# B7D_1_1.net
KiCad netlist of a schematic drawn in EAGLE
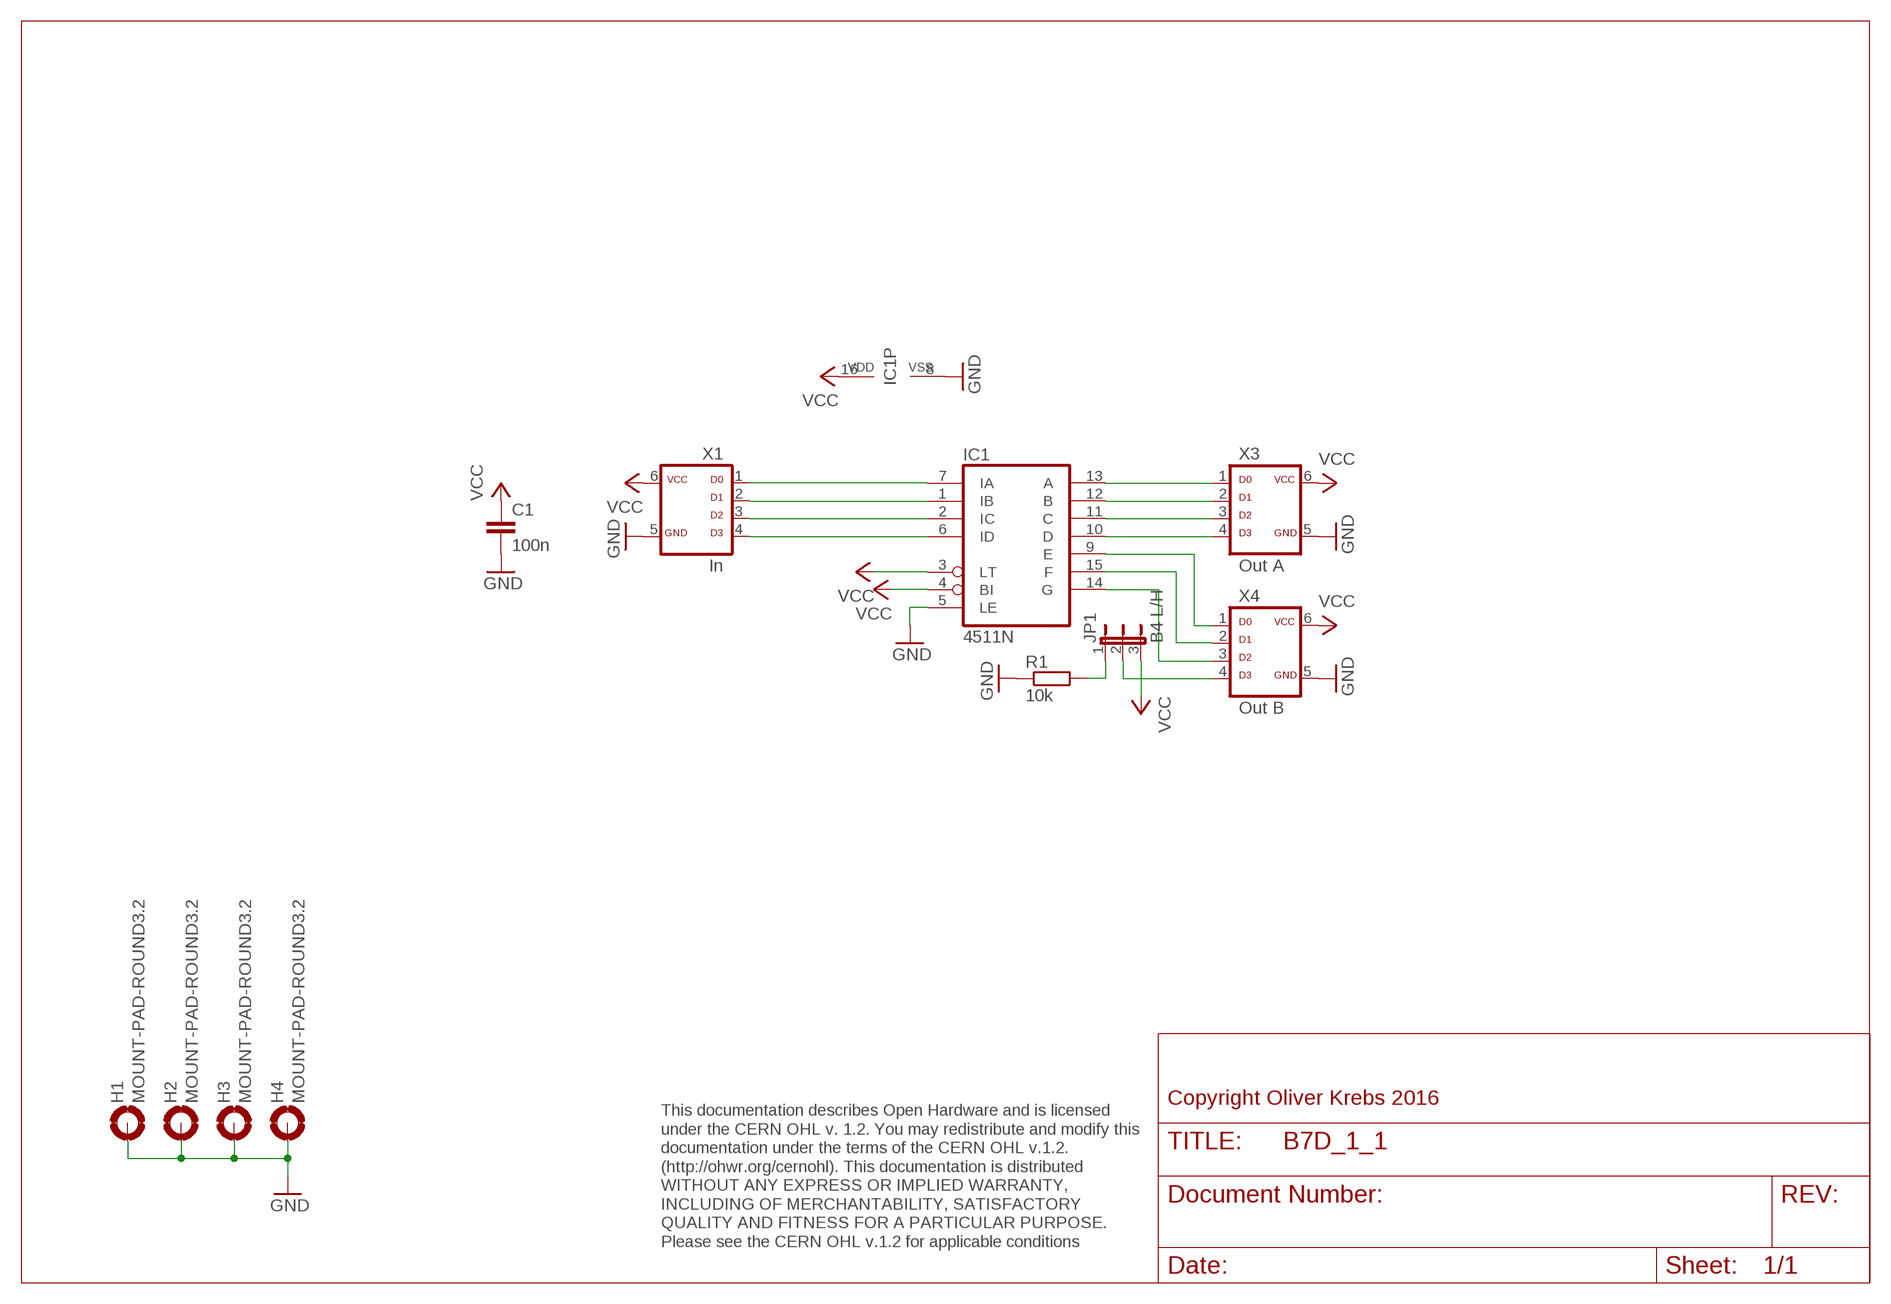
[diagram p0: schematic, sheet 1]

(export (version "E")
  (design (tool "Eeschema 10.0.6"))
  (components
    (comp (ref "C1")
      (value "100n")
      (footprint "eagle-import:C050-025X075")
      (libsource (lib "eagle-import") (part "C-EU050-025X075"))
    )
    (comp (ref "H1")
      (value "MOUNT-PAD-ROUND3.2")
      (footprint "eagle-import:3,2-PAD")
      (libsource (lib "eagle-import") (part "MOUNT-PAD-ROUND3.2"))
    )
    (comp (ref "H2")
      (value "MOUNT-PAD-ROUND3.2")
      (footprint "eagle-import:3,2-PAD")
      (libsource (lib "eagle-import") (part "MOUNT-PAD-ROUND3.2"))
    )
    (comp (ref "H3")
      (value "MOUNT-PAD-ROUND3.2")
      (footprint "eagle-import:3,2-PAD")
      (libsource (lib "eagle-import") (part "MOUNT-PAD-ROUND3.2"))
    )
    (comp (ref "H4")
      (value "MOUNT-PAD-ROUND3.2")
      (footprint "eagle-import:3,2-PAD")
      (libsource (lib "eagle-import") (part "MOUNT-PAD-ROUND3.2"))
    )
    (comp (ref "IC1")
      (value "4511N")
      (footprint "eagle-import:DIL16")
      (libsource (lib "eagle-import") (part "4511N"))
    )
    (comp (ref "JP1")
      (value "B4 L/H")
      (footprint "eagle-import:JP2")
      (libsource (lib "eagle-import") (part "JP2E"))
    )
    (comp (ref "R1")
      (value "10k")
      (footprint "eagle-import:0207_10")
      (libsource (lib "eagle-import") (part "R-EU_0207/10"))
    )
    (comp (ref "X1")
      (value "In")
      (footprint "eagle-import:ML-6")
      (libsource (lib "eagle-import") (part "ML6D"))
    )
    (comp (ref "X3")
      (value "Out A")
      (footprint "eagle-import:ML-6")
      (libsource (lib "eagle-import") (part "ML6D"))
    )
    (comp (ref "X4")
      (value "Out B")
      (footprint "eagle-import:ML-6")
      (libsource (lib "eagle-import") (part "ML6D"))
    )
  )
  (nets
    (net (code "1") (name "GND") (class "Default")
      (node (ref "C1") (pin "2") (pinfunction "2_2") (pintype "passive"))
      (node (ref "H1") (pin "B3,2") (pinfunction "MOUNT_B3,2") (pintype "passive"))
      (node (ref "H2") (pin "B3,2") (pinfunction "MOUNT_B3,2") (pintype "passive"))
      (node (ref "H3") (pin "B3,2") (pinfunction "MOUNT_B3,2") (pintype "passive"))
      (node (ref "H4") (pin "B3,2") (pinfunction "MOUNT_B3,2") (pintype "passive"))
      (node (ref "IC1") (pin "5") (pinfunction "LE_5") (pintype "input"))
      (node (ref "IC1") (pin "8") (pinfunction "VSS_8") (pintype "power_in"))
      (node (ref "R1") (pin "1") (pinfunction "1_1") (pintype "passive"))
      (node (ref "X1") (pin "5") (pinfunction "5_5") (pintype "passive"))
      (node (ref "X3") (pin "5") (pinfunction "5_5") (pintype "passive"))
      (node (ref "X4") (pin "5") (pinfunction "5_5") (pintype "passive"))
    )
    (net (code "2") (name "Net-(IC1A-A)") (class "Default")
      (node (ref "IC1") (pin "13") (pinfunction "A_13") (pintype "output"))
      (node (ref "X3") (pin "1") (pinfunction "1_1") (pintype "passive"))
    )
    (net (code "3") (name "Net-(IC1A-B)") (class "Default")
      (node (ref "IC1") (pin "12") (pinfunction "B_12") (pintype "output"))
      (node (ref "X3") (pin "2") (pinfunction "2_2") (pintype "passive"))
    )
    (net (code "4") (name "Net-(IC1A-C)") (class "Default")
      (node (ref "IC1") (pin "11") (pinfunction "C_11") (pintype "output"))
      (node (ref "X3") (pin "3") (pinfunction "3_3") (pintype "passive"))
    )
    (net (code "5") (name "Net-(IC1A-D)") (class "Default")
      (node (ref "IC1") (pin "10") (pinfunction "D_10") (pintype "output"))
      (node (ref "X3") (pin "4") (pinfunction "4_4") (pintype "passive"))
    )
    (net (code "6") (name "Net-(IC1A-E)") (class "Default")
      (node (ref "IC1") (pin "9") (pinfunction "E_9") (pintype "output"))
      (node (ref "X4") (pin "1") (pinfunction "1_1") (pintype "passive"))
    )
    (net (code "7") (name "Net-(IC1A-F)") (class "Default")
      (node (ref "IC1") (pin "15") (pinfunction "F_15") (pintype "output"))
      (node (ref "X4") (pin "2") (pinfunction "2_2") (pintype "passive"))
    )
    (net (code "8") (name "Net-(IC1A-G)") (class "Default")
      (node (ref "IC1") (pin "14") (pinfunction "G_14") (pintype "output"))
      (node (ref "X4") (pin "3") (pinfunction "3_3") (pintype "passive"))
    )
    (net (code "9") (name "Net-(IC1A-IA)") (class "Default")
      (node (ref "IC1") (pin "7") (pinfunction "IA_7") (pintype "input"))
      (node (ref "X1") (pin "1") (pinfunction "1_1") (pintype "passive"))
    )
    (net (code "10") (name "Net-(IC1A-IB)") (class "Default")
      (node (ref "IC1") (pin "1") (pinfunction "IB_1") (pintype "input"))
      (node (ref "X1") (pin "2") (pinfunction "2_2") (pintype "passive"))
    )
    (net (code "11") (name "Net-(IC1A-IC)") (class "Default")
      (node (ref "IC1") (pin "2") (pinfunction "IC_2") (pintype "input"))
      (node (ref "X1") (pin "3") (pinfunction "3_3") (pintype "passive"))
    )
    (net (code "12") (name "Net-(IC1A-ID)") (class "Default")
      (node (ref "IC1") (pin "6") (pinfunction "ID_6") (pintype "input"))
      (node (ref "X1") (pin "4") (pinfunction "4_4") (pintype "passive"))
    )
    (net (code "13") (name "Net-(JP1-Pad1)") (class "Default")
      (node (ref "JP1") (pin "1") (pinfunction "1_1") (pintype "passive"))
      (node (ref "R1") (pin "2") (pinfunction "2_2") (pintype "passive"))
    )
    (net (code "14") (name "Net-(JP1-Pad2)") (class "Default")
      (node (ref "JP1") (pin "2") (pinfunction "2_2") (pintype "passive"))
      (node (ref "X4") (pin "4") (pinfunction "4_4") (pintype "passive"))
    )
    (net (code "15") (name "VCC") (class "Default")
      (node (ref "C1") (pin "1") (pinfunction "1_1") (pintype "passive"))
      (node (ref "IC1") (pin "16") (pinfunction "VDD_16") (pintype "power_in"))
      (node (ref "IC1") (pin "3") (pinfunction "LT_3") (pintype "input"))
      (node (ref "IC1") (pin "4") (pinfunction "BI_4") (pintype "input"))
      (node (ref "JP1") (pin "3") (pinfunction "3_3") (pintype "passive"))
      (node (ref "X1") (pin "6") (pinfunction "6_6") (pintype "passive"))
      (node (ref "X3") (pin "6") (pinfunction "6_6") (pintype "passive"))
      (node (ref "X4") (pin "6") (pinfunction "6_6") (pintype "passive"))
    )
  )
)
